# BATTERY-CONTROL.net
KiCad netlist of a schematic drawn in Altium Designer
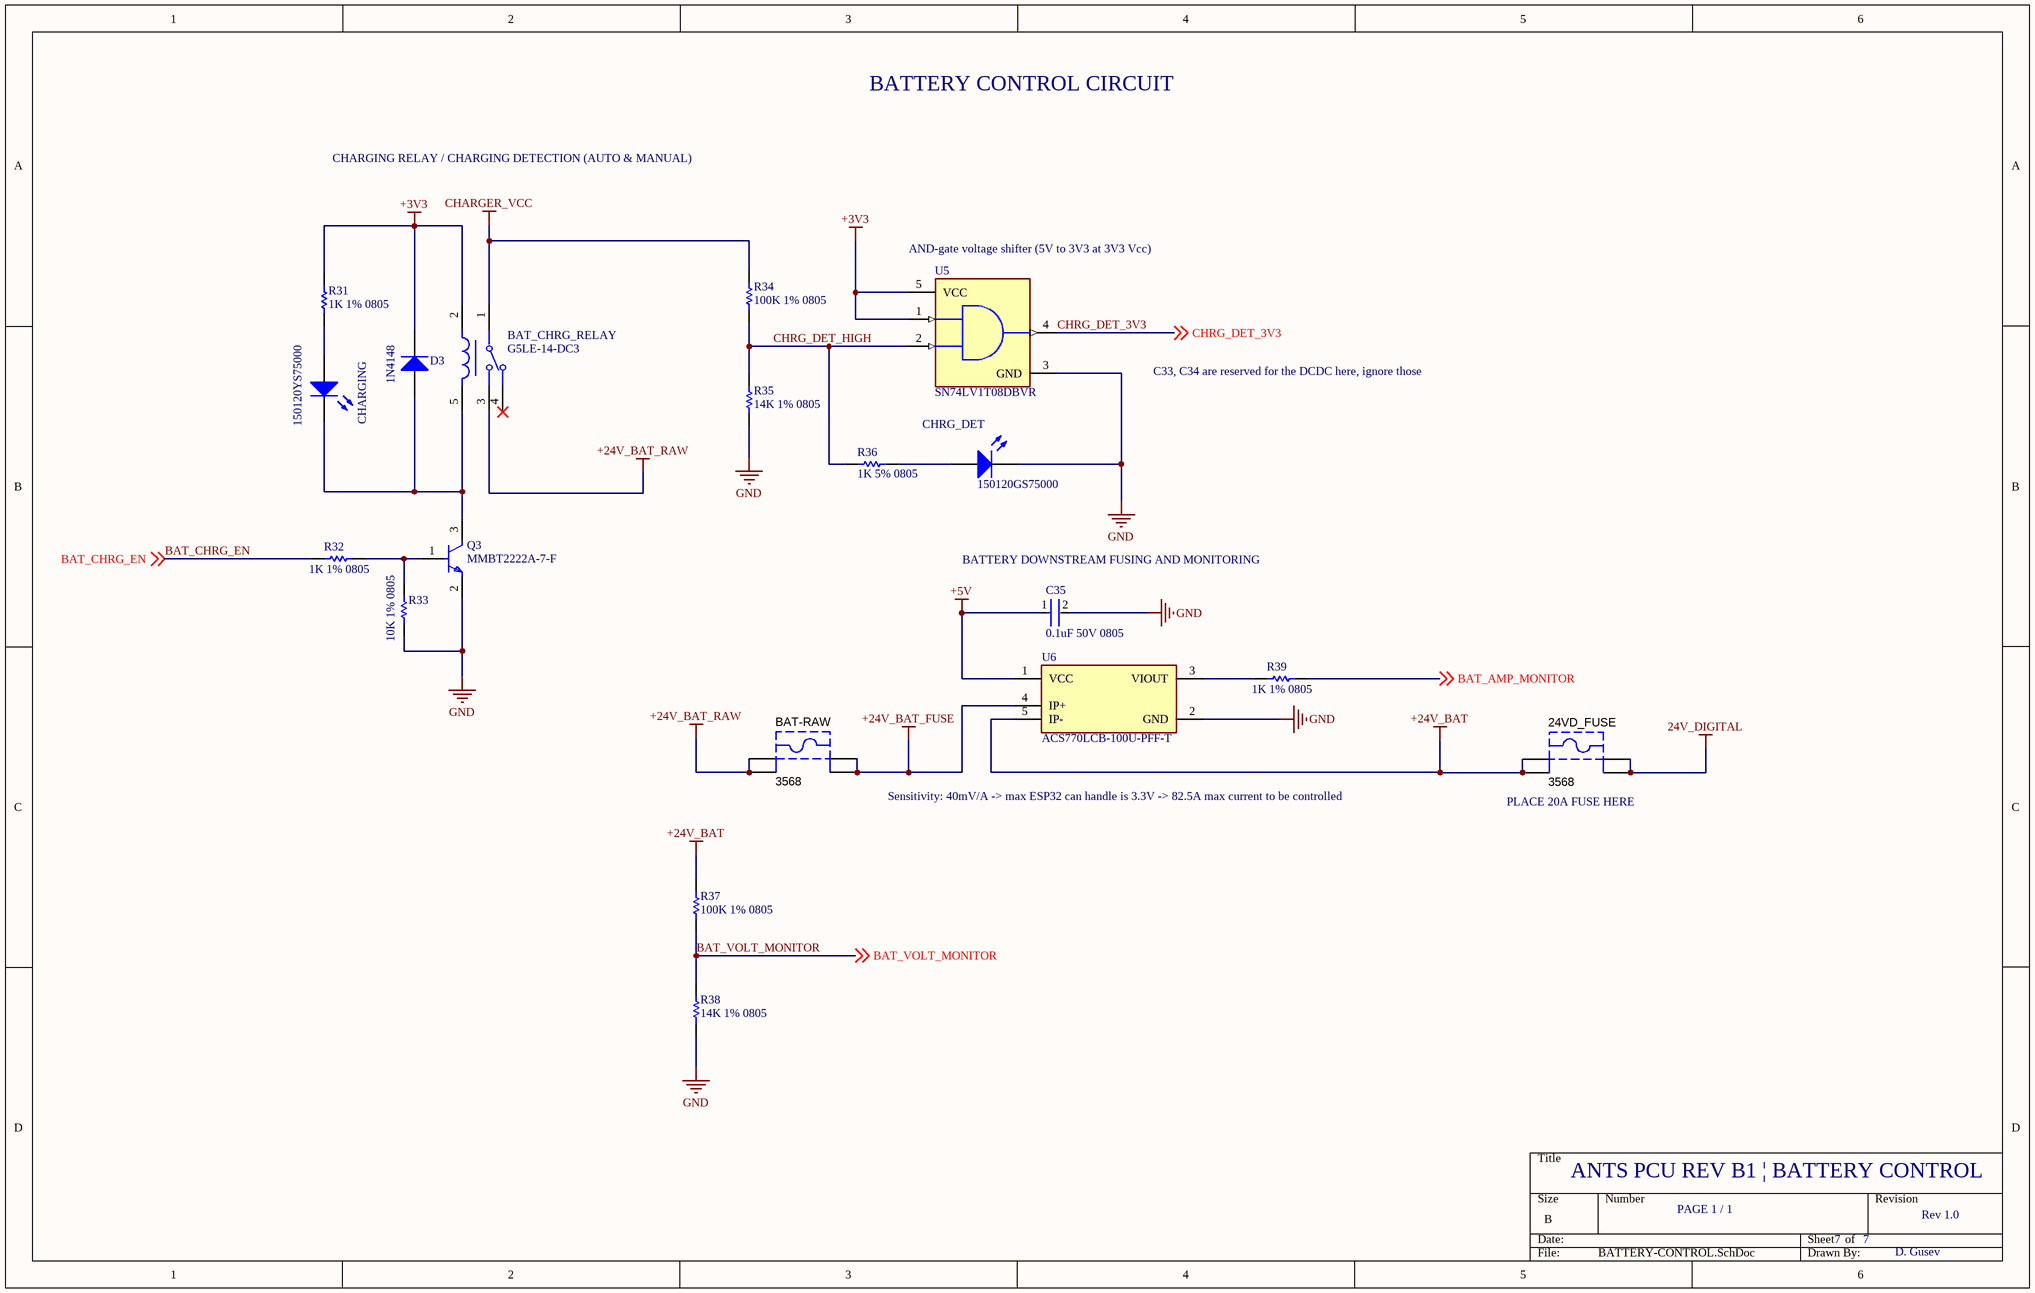
[diagram p0: BATTERY-CONTROL.SchDoc]

(export (version "E")
  (design (tool "Eeschema 10.0.6"))
  (components
    (comp (ref "24VD_FUSE")
      (value "3568")
      (footprint "KSTN-3568_V")
      (description "Fuse Holder, 20 A, 500 V, -50 to 145 degC, 4-Pin THD, RoHS")
      (fields (field (name "MANUFACTURER") "Keystone"))
      (libsource (lib "Altium Content Vault") (part "FUSE_HOLDER-4"))
    )
    (comp (ref "BAT-RAW")
      (value "3568")
      (footprint "KSTN-3568_V")
      (description "Fuse Holder, 20 A, 500 V, -50 to 145 degC, 4-Pin THD, RoHS")
      (fields (field (name "MANUFACTURER") "Keystone"))
      (libsource (lib "") (part "FUSE_HOLDER-4_1"))
    )
    (comp (ref "BAT_CHRG_RELAY")
      (value "G5LE-14-DC3")
      (footprint "FP-G5LE-14-DC5-MFG")
      (description "RELAY GEN PURPOSE SPDT 10A 5V")
      (fields
        (field (name "OCTOPART") "https://octopart.com/g5le-14-dc5-omron-28829")
        (field (name "MANUFACTURER") "Omron")
      )
      (libsource (lib "Altium Content Vault") (part "c03b8d08e5d02e70a6880f365e34168"))
    )
    (comp (ref "C35")
      (value "0.1uF 50V 0805")
      (footprint "FP-C0805C-DN-MFG")
      (description "CAP CER 0.1UF 50V X7R 0805")
      (fields
        (field (name "MANUFACTURER PART NUMBER") "C0805C104K5RACTU")
        (field (name "MANUFACTURER") "KEMET")
      )
      (libsource (lib "Altium Content Vault") (part "b4654b650e69147ec39a6b967a45e02"))
    )
    (comp (ref "CHARGING")
      (value "150120YS75000")
      (footprint "1206_A")
      (description "SMD mono-color Chip LED, WL-SMCW, Yellow")
      (fields (field (name "MANUFACTURER") "Wuerth Elektronik"))
      (libsource (lib "Altium Content Vault") (part "WE-LED_K1A2-2"))
    )
    (comp (ref "CHRG_DET")
      (value "150120GS75000")
      (footprint "1206_A")
      (description "SMD mono-color Chip LED, WL-SMCW, Green")
      (fields (field (name "MANUFACTURER") "Wuerth Elektronik"))
      (libsource (lib "Altium Content Vault") (part "WE-LED_K1A2-2"))
    )
    (comp (ref "D3")
      (value "1N4148")
      (footprint "NXP-SOD27-2_V")
      (description "High-speed Diode, 100 V, 450 mA, 2-Pin SOD27, RoHS")
      (fields (field (name "MANUFACTURER") "NXP Semiconductors"))
      (libsource (lib "Altium Content Vault") (part "NXP-A1K2-2"))
    )
    (comp (ref "Q3")
      (value "MMBT2222A-7-F")
      (footprint "FP-SOT23-IPC_A")
      (description "TRANS NPN 40V 0.6A SMD SOT23-3")
      (fields (field (name "VOLTAGE") "40V"))
      (libsource (lib "Altium Content Vault") (part "b44e953556f554d0102664c7d152cb4"))
    )
    (comp (ref "R31")
      (value "1K 1% 0805")
      (footprint "RESC2013X60X35ML10T20")
      (description "Chip Resistor, 1 KOhm, +/- 1%, 125 mW, -55 to 155 degC, 0805 (2012 Metric), RoHS, Tape and Reel")
      (fields (field (name "TOLERANCE") "1%") (field (name "MANUFACTURER") "Yageo"))
      (libsource (lib "Altium Content Vault") (part "RES-2"))
    )
    (comp (ref "R32")
      (value "1K 1% 0805")
      (footprint "RESC2013X60X35ML10T20")
      (description "Chip Resistor, 1 KOhm, +/- 1%, 125 mW, -55 to 155 degC, 0805 (2012 Metric), RoHS, Tape and Reel")
      (fields (field (name "TOLERANCE") "1%") (field (name "MANUFACTURER") "Yageo"))
      (libsource (lib "Altium Content Vault") (part "RES-2"))
    )
    (comp (ref "R33")
      (value "10K 1% 0805")
      (footprint "RESC2013X60X35NL10T20")
      (description "Chip Resistor, 10 KOhm, +/- 1%, 0.125 W, -55 to 155 degC, 0805 (2012 Metric), RoHS, Tape and Reel")
      (fields (field (name "MANUFACTURER") "Yageo"))
      (libsource (lib "Altium Content Vault") (part "RES-2"))
    )
    (comp (ref "R34")
      (value "100K 1% 0805")
      (footprint "RESC2013X60X35ML10T20")
      (description "Chip Resistor, 100 KOhm, +/- 1%, 0.125 W, -55 to 155 degC, 0805 (2012 Metric), RoHS, Tape and Reel")
      (fields (field (name "MANUFACTURER") "Yageo") (field (name "TOLERANCE") "1%"))
      (libsource (lib "Altium Content Vault") (part "RES-2"))
    )
    (comp (ref "R35")
      (value "14K 1% 0805")
      (footprint "RESC2013X60X35LL10T20")
      (fields (field (name "PART NUMBER") "RC0805FR-0714KL") (field (name "MANUFACTURER") "Yageo"))
      (libsource (lib "Altium Content Vault") (part "RES"))
    )
    (comp (ref "R36")
      (value "1K 5% 0805")
      (footprint "RESC2013X60X40ML20T25")
      (fields (field (name "PART NUMBER") "ERA6AEB123V") (field (name "MANUFACTURER") "Panasonic"))
      (libsource (lib "Altium Content Vault") (part "RES"))
    )
    (comp (ref "R37")
      (value "100K 1% 0805")
      (footprint "RESC2013X60X35ML10T20")
      (description "Chip Resistor, 100 KOhm, +/- 1%, 0.125 W, -55 to 155 degC, 0805 (2012 Metric), RoHS, Tape and Reel")
      (fields (field (name "MANUFACTURER") "Yageo") (field (name "TOLERANCE") "1%"))
      (libsource (lib "Altium Content Vault") (part "RES-2"))
    )
    (comp (ref "R38")
      (value "14K 1% 0805")
      (footprint "RESC2013X60X35LL10T20")
      (fields (field (name "PART NUMBER") "RC0805FR-0714KL") (field (name "MANUFACTURER") "Yageo"))
      (libsource (lib "Altium Content Vault") (part "RES"))
    )
    (comp (ref "R39")
      (value "1K 1% 0805")
      (footprint "RESC2013X60X35ML10T20")
      (description "Chip Resistor, 1 KOhm, +/- 1%, 125 mW, -55 to 155 degC, 0805 (2012 Metric), RoHS, Tape and Reel")
      (fields (field (name "TOLERANCE") "1%") (field (name "MANUFACTURER") "Yageo"))
      (libsource (lib "Altium Content Vault") (part "RES-2"))
    )
    (comp (ref "U5")
      (value "SN74LV1T08DBVR")
      (footprint "FP-DBV0005A-IPC_B")
      (description "IC GATE AND 1CH 2-INP SOT23-5")
      (libsource (lib "Altium Content Vault") (part "98d1ee7761b7c84c2afddac8daf2ac5"))
    )
    (comp (ref "U6")
      (value "ACS770LCB-100U-PFF-T")
      (footprint "ACS770LCB-100U-PFF-T")
      (description "SENSOR CURRENT HALL 100A DC")
      (libsource (lib "ANTS-PCU-B1") (part "ACS770LCB-100U-PFF-T"))
    )
  )
  (nets
    (net (code "1") (name "+3V3") (class "Default")
      (node (ref "BAT_CHRG_RELAY") (pin "2") (pinfunction "2_2") (pintype "passive"))
      (node (ref "D3") (pin "2") (pinfunction "K_2") (pintype "passive"))
      (node (ref "R31") (pin "1") (pinfunction "1_1") (pintype "passive"))
      (node (ref "U5") (pin "1") (pinfunction "A_1") (pintype "input"))
      (node (ref "U5") (pin "5") (pinfunction "VCC_5") (pintype "power_in"))
    )
    (net (code "2") (name "+5V") (class "Default")
      (node (ref "C35") (pin "1") (pinfunction "1_1") (pintype "passive"))
      (node (ref "U6") (pin "1") (pinfunction "VCC_1") (pintype "power_in"))
    )
    (net (code "3") (name "+24V_BAT") (class "Default")
      (node (ref "24VD_FUSE") (pin "1") (pinfunction "1_1") (pintype "passive"))
      (node (ref "24VD_FUSE") (pin "2") (pinfunction "2_2") (pintype "passive"))
      (node (ref "R37") (pin "2") (pinfunction "2_2") (pintype "passive"))
      (node (ref "U6") (pin "5") (pinfunction "IP-_5") (pintype "passive"))
    )
    (net (code "4") (name "+24V_BAT_FUSE") (class "Default")
      (node (ref "BAT-RAW") (pin "1") (pinfunction "1_1") (pintype "passive"))
      (node (ref "BAT-RAW") (pin "2") (pinfunction "2_2") (pintype "passive"))
      (node (ref "U6") (pin "4") (pinfunction "IP+_4") (pintype "passive"))
    )
    (net (code "5") (name "+24V_BAT_RAW") (class "Default")
      (node (ref "BAT-RAW") (pin "3") (pinfunction "3_3") (pintype "passive"))
      (node (ref "BAT-RAW") (pin "4") (pinfunction "4_4") (pintype "passive"))
      (node (ref "BAT_CHRG_RELAY") (pin "3") (pinfunction "3_3") (pintype "passive"))
    )
    (net (code "6") (name "/CHRG_DET_HIGH") (class "Default")
      (node (ref "R34") (pin "1") (pinfunction "1_1") (pintype "passive"))
      (node (ref "R35") (pin "2") (pinfunction "2_2") (pintype "passive"))
      (node (ref "R36") (pin "2") (pinfunction "2_2") (pintype "passive"))
      (node (ref "U5") (pin "2") (pinfunction "B_2") (pintype "input"))
    )
    (net (code "7") (name "24V_DIGITAL") (class "Default")
      (node (ref "24VD_FUSE") (pin "3") (pinfunction "3_3") (pintype "passive"))
      (node (ref "24VD_FUSE") (pin "4") (pinfunction "4_4") (pintype "passive"))
    )
    (net (code "8") (name "BAT_AMP_MONITOR") (class "Default")
      (node (ref "R39") (pin "2") (pinfunction "2_2") (pintype "passive"))
    )
    (net (code "9") (name "BAT_CHRG_EN") (class "Default")
      (node (ref "R32") (pin "1") (pinfunction "1_1") (pintype "passive"))
    )
    (net (code "10") (name "BAT_VOLT_MONITOR") (class "Default")
      (node (ref "R37") (pin "1") (pinfunction "1_1") (pintype "passive"))
      (node (ref "R38") (pin "2") (pinfunction "2_2") (pintype "passive"))
    )
    (net (code "11") (name "CHARGER_VCC") (class "Default")
      (node (ref "BAT_CHRG_RELAY") (pin "1") (pinfunction "1_1") (pintype "passive"))
      (node (ref "R34") (pin "2") (pinfunction "2_2") (pintype "passive"))
    )
    (net (code "12") (name "CHRG_DET_3V3") (class "Default")
      (node (ref "U5") (pin "4") (pinfunction "Y_4") (pintype "output"))
    )
    (net (code "13") (name "GND") (class "Default")
      (node (ref "C35") (pin "2") (pinfunction "2_2") (pintype "passive"))
      (node (ref "CHRG_DET") (pin "1") (pinfunction "K_1") (pintype "passive"))
      (node (ref "Q3") (pin "2") (pinfunction "E_2") (pintype "passive"))
      (node (ref "R33") (pin "1") (pinfunction "1_1") (pintype "passive"))
      (node (ref "R35") (pin "1") (pinfunction "1_1") (pintype "passive"))
      (node (ref "R38") (pin "1") (pinfunction "1_1") (pintype "passive"))
      (node (ref "U5") (pin "3") (pinfunction "GND_3") (pintype "power_in"))
      (node (ref "U6") (pin "2") (pinfunction "GND_2") (pintype "power_in"))
    )
    (net (code "14") (name "Net-(CHARGING-A)") (class "Default")
      (node (ref "CHARGING") (pin "2") (pinfunction "A_2") (pintype "passive"))
      (node (ref "R31") (pin "2") (pinfunction "2_2") (pintype "passive"))
    )
    (net (code "15") (name "Net-(CHARGING-K)") (class "Default")
      (node (ref "BAT_CHRG_RELAY") (pin "5") (pinfunction "5_5") (pintype "passive"))
      (node (ref "CHARGING") (pin "1") (pinfunction "K_1") (pintype "passive"))
      (node (ref "D3") (pin "1") (pinfunction "A_1") (pintype "passive"))
      (node (ref "Q3") (pin "3") (pinfunction "C_3") (pintype "passive"))
    )
    (net (code "16") (name "Net-(CHRG_DET-A)") (class "Default")
      (node (ref "CHRG_DET") (pin "2") (pinfunction "A_2") (pintype "passive"))
      (node (ref "R36") (pin "1") (pinfunction "1_1") (pintype "passive"))
    )
    (net (code "17") (name "Net-(Q3-B)") (class "Default")
      (node (ref "Q3") (pin "1") (pinfunction "B_1") (pintype "passive"))
      (node (ref "R32") (pin "2") (pinfunction "2_2") (pintype "passive"))
      (node (ref "R33") (pin "2") (pinfunction "2_2") (pintype "passive"))
    )
    (net (code "18") (name "Net-(U6-VIOUT)") (class "Default")
      (node (ref "R39") (pin "1") (pinfunction "1_1") (pintype "passive"))
      (node (ref "U6") (pin "3") (pinfunction "VIOUT_3") (pintype "passive"))
    )
    (net (code "19") (name "unconnected-(BAT_CHRG_RELAY-Pad4)") (class "Default")
      (node (ref "BAT_CHRG_RELAY") (pin "4") (pinfunction "4_4") (pintype "passive+no_connect"))
    )
  )
)
